# 10_-_CPU_-_JTAG_CONTROL.net
KiCad netlist of a schematic drawn in Altium Designer
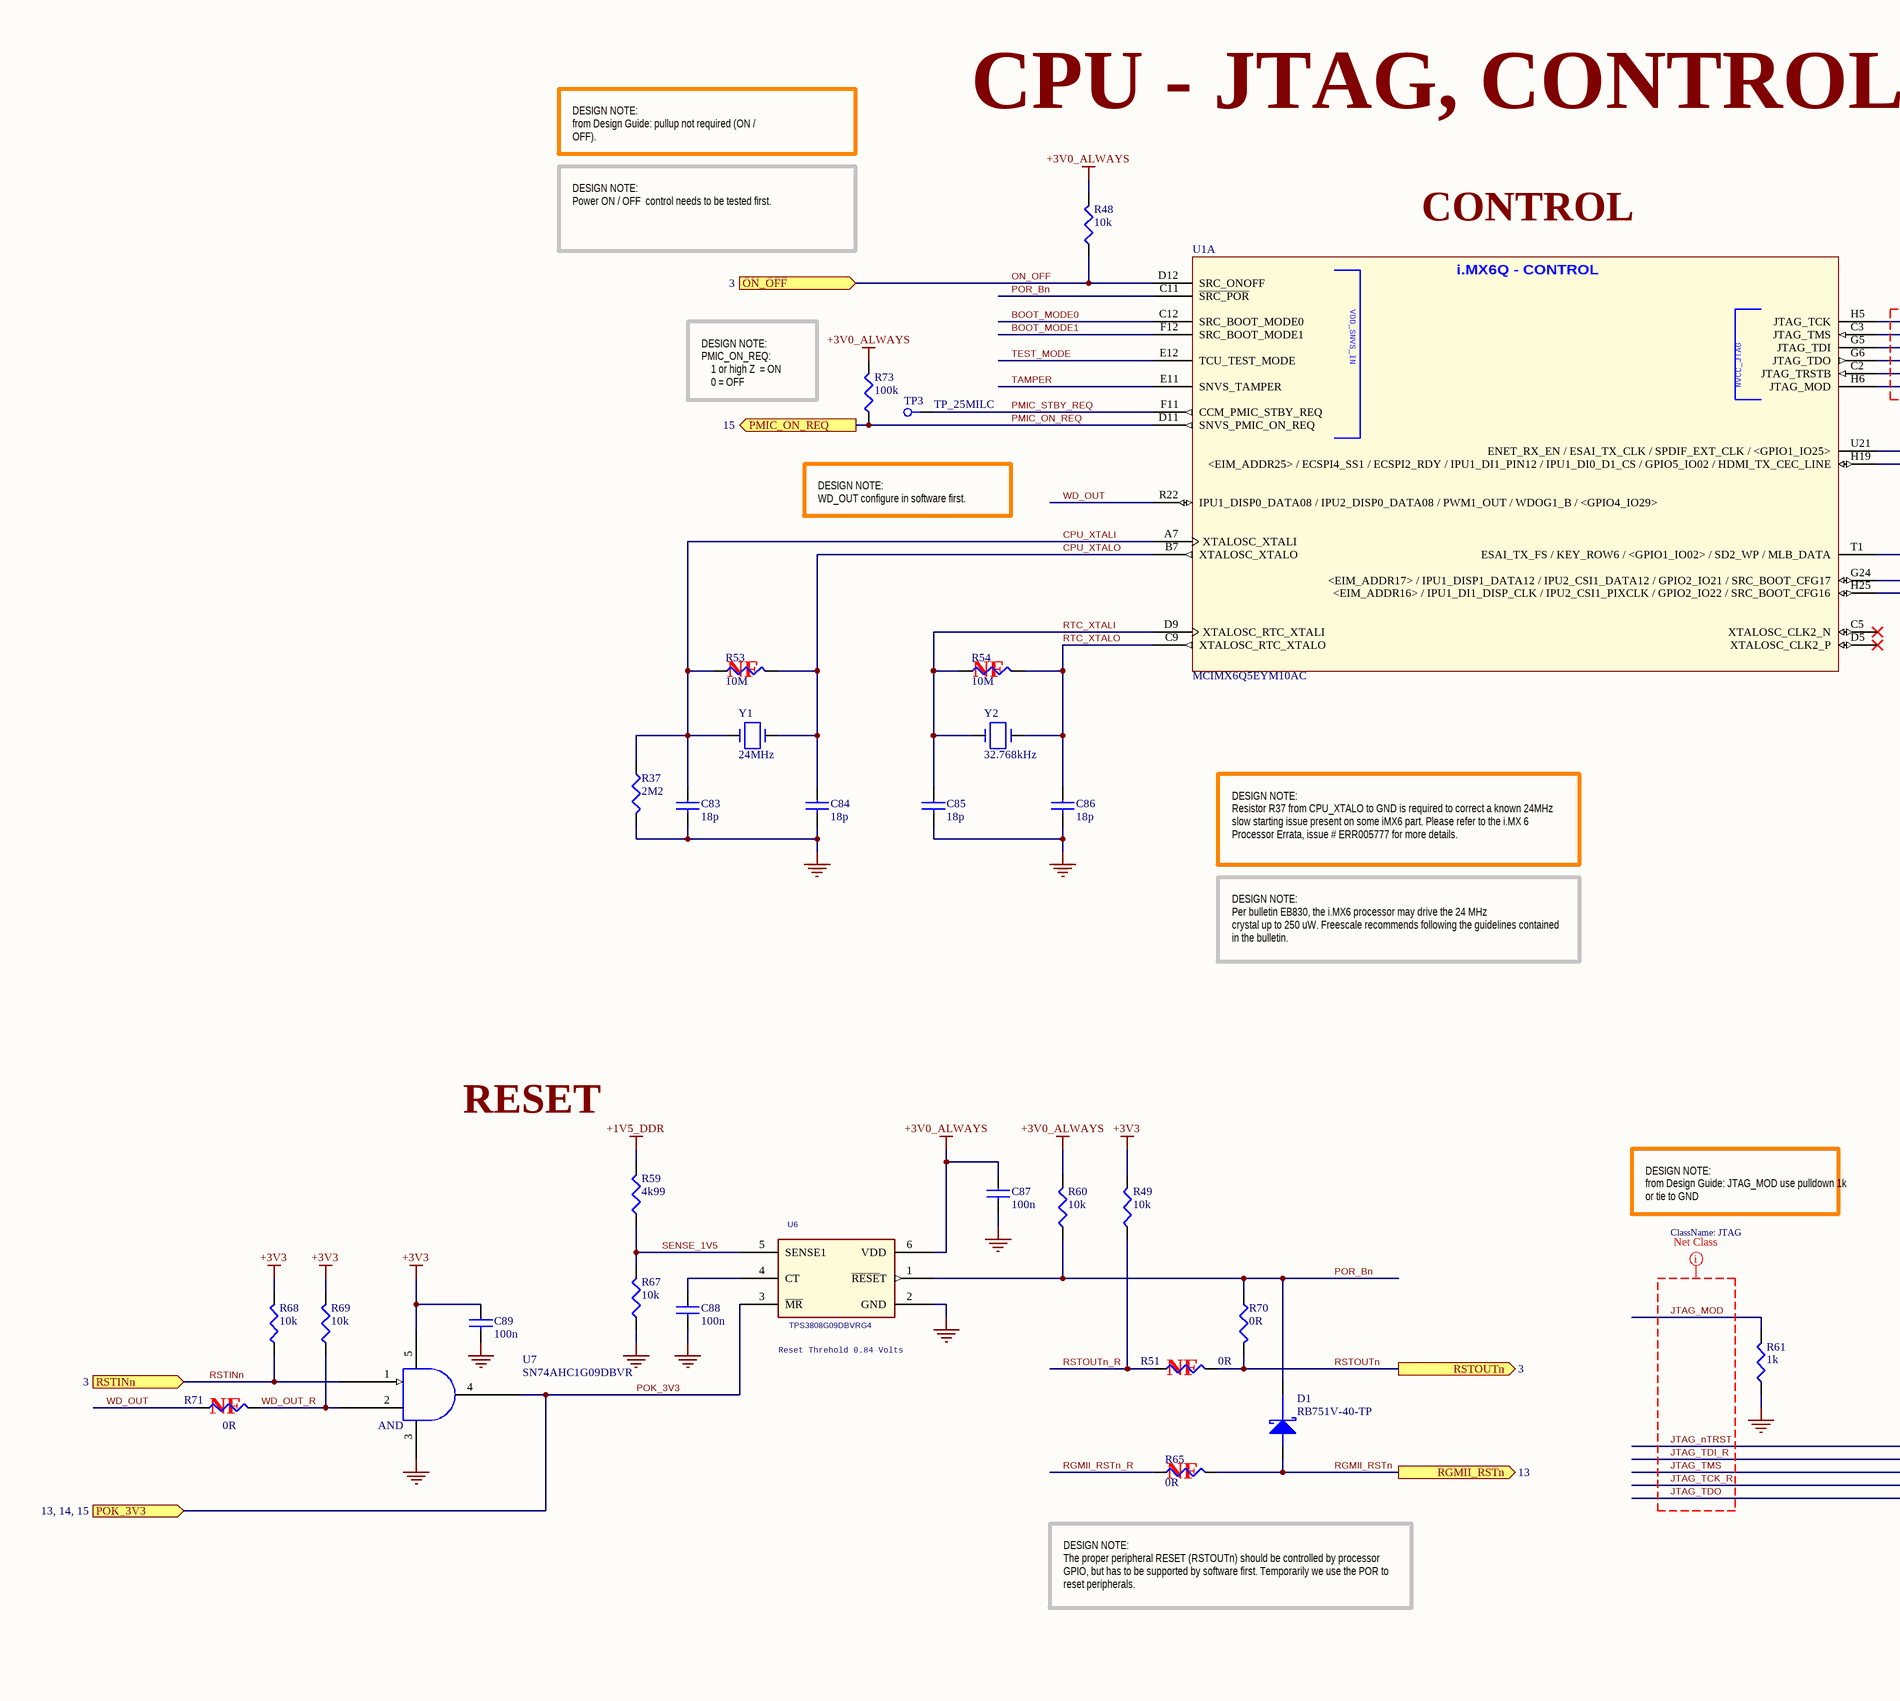
[diagram p0: [10] - CPU - JTAG, CONTROL.SchDoc, left]
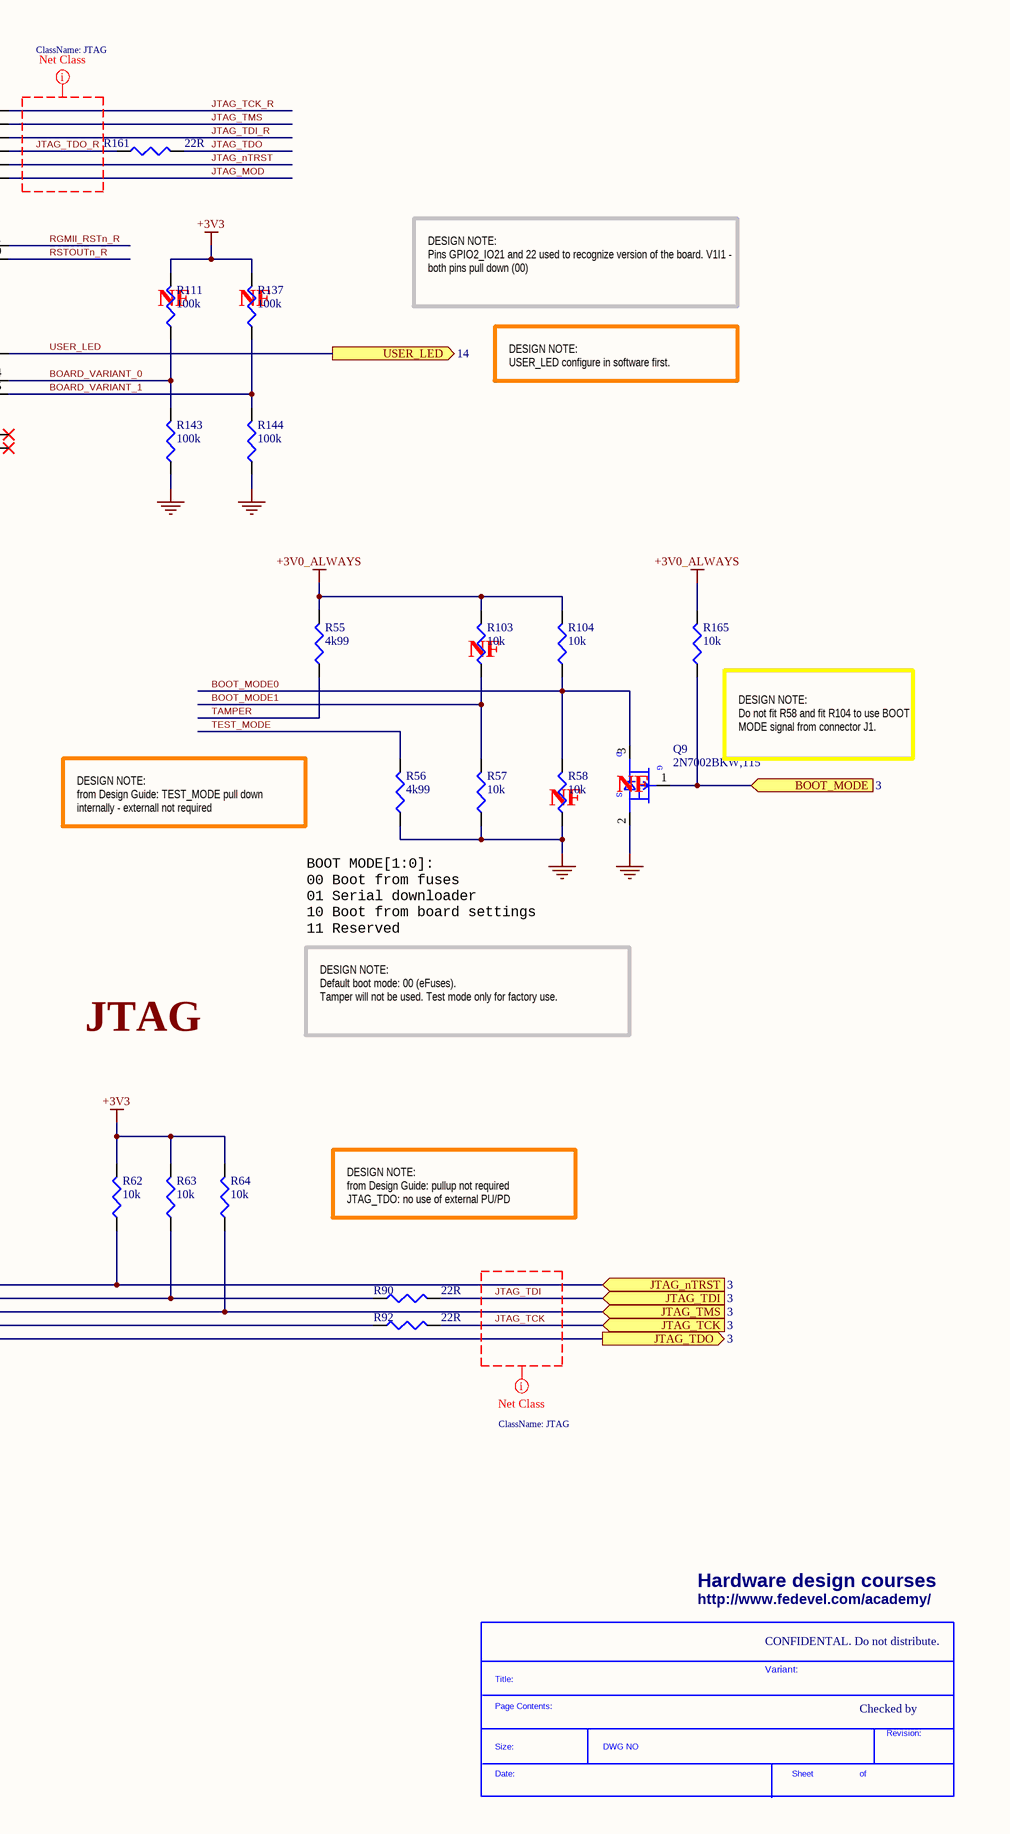
[diagram p1: [10] - CPU - JTAG, CONTROL.SchDoc, right]

(export (version "E")
  (design (tool "Eeschema 10.0.6"))
  (components
    (comp (ref "C83")
      (value "18p")
      (footprint "C0402")
      (description "CAP CER 18PF 50V C0G 5% 0402")
      (fields
        (field (name "MANUFACTURER") "TDK Corporation")
        (field (name "MANUFACTURER PART NUMBER") "C1005C0G1H180J")
      )
      (libsource (lib "iMX6 Rex_V1I1") (part "C1005C0G1H180J"))
    )
    (comp (ref "C84")
      (value "18p")
      (footprint "C0402")
      (description "CAP CER 18PF 50V C0G 5% 0402")
      (fields
        (field (name "MANUFACTURER") "TDK Corporation")
        (field (name "MANUFACTURER PART NUMBER") "C1005C0G1H180J")
      )
      (libsource (lib "iMX6 Rex_V1I1") (part "C1005C0G1H180J"))
    )
    (comp (ref "C85")
      (value "18p")
      (footprint "C0402")
      (description "CAP CER 18PF 50V C0G 5% 0402")
      (fields
        (field (name "MANUFACTURER") "TDK Corporation")
        (field (name "MANUFACTURER PART NUMBER") "C1005C0G1H180J")
      )
      (libsource (lib "iMX6 Rex_V1I1") (part "C1005C0G1H180J"))
    )
    (comp (ref "C86")
      (value "18p")
      (footprint "C0402")
      (description "CAP CER 18PF 50V C0G 5% 0402")
      (fields
        (field (name "MANUFACTURER") "TDK Corporation")
        (field (name "MANUFACTURER PART NUMBER") "C1005C0G1H180J")
      )
      (libsource (lib "iMX6 Rex_V1I1") (part "C1005C0G1H180J"))
    )
    (comp (ref "C87")
      (value "100n")
      (footprint "C0402")
      (description "CAP CER .10UF 50V X5R 10% 0402")
      (fields
        (field (name "MANUFACTURER") "TDK Corporation")
        (field (name "MANUFACTURER PART NUMBER") "C1005X5R1H104K")
      )
      (libsource (lib "iMX6 Rex_V1I1") (part "C1005X5R1H104K"))
    )
    (comp (ref "C88")
      (value "100n")
      (footprint "C0402")
      (description "CAP CER .10UF 50V X5R 10% 0402")
      (fields
        (field (name "MANUFACTURER") "TDK Corporation")
        (field (name "MANUFACTURER PART NUMBER") "C1005X5R1H104K")
      )
      (libsource (lib "iMX6 Rex_V1I1") (part "C1005X5R1H104K"))
    )
    (comp (ref "C89")
      (value "100n")
      (footprint "C0402")
      (description "CAP CER .10UF 50V X5R 10% 0402")
      (fields
        (field (name "MANUFACTURER") "TDK Corporation")
        (field (name "MANUFACTURER PART NUMBER") "C1005X5R1H104K")
      )
      (libsource (lib "iMX6 Rex_V1I1") (part "C1005X5R1H104K"))
    )
    (comp (ref "D1")
      (value "RB751V-40-TP")
      (footprint "SOD323")
      (description "DIODE SCHTKY 30MA 30V SOD-323")
      (fields
        (field (name "MANUFACTURER") "Micro Commercial Co")
        (field (name ".CHECKED PCB") "RF")
        (field (name ".CHECKED SCH") "RF")
      )
      (libsource (lib "iMX6 Rex_V1I1") (part "RB751V-40-TP"))
    )
    (comp (ref "Q9")
      (value "2N7002BKW,115")
      (footprint "SC70_SOT323")
      (description "MOSFET N-CH 60V 310MA SOT323")
      (fields
        (field (name "MANUFACTURER") "NXP Semiconductors")
        (field (name ".CHECKED PCB") "RF")
        (field (name ".CHECKED SCH") "RF")
      )
      (libsource (lib "iMX6 Rex_V1I1") (part "2N7002BKW,115"))
    )
    (comp (ref "R37")
      (value "2M2")
      (footprint "R0402")
      (description "RES 2.20M OHM 1/16W 1% 0402 SMD")
      (fields
        (field (name "MANUFACTURER") "Vishay Dale")
        (field (name "MANUFACTURER PART NUMBER") "CRCW04022M20FKED")
        (field (name ".CREATOR") "MM")
      )
      (libsource (lib "iMX6 Rex_V1I1") (part "CRCW04022M20FKED"))
    )
    (comp (ref "R48")
      (value "10k")
      (footprint "R0402")
      (description "RES 10.0K OHM 1/16W 1% 0402 SMD")
      (fields
        (field (name "MANUFACTURER") "Yageo")
        (field (name "MANUFACTURER PART NUMBER") "RC0402FR-0710KL")
      )
      (libsource (lib "iMX6 Rex_V1I1") (part "RC0402FR-0710KL"))
    )
    (comp (ref "R49")
      (value "10k")
      (footprint "R0402")
      (description "RES 10.0K OHM 1/16W 1% 0402 SMD")
      (fields
        (field (name "MANUFACTURER") "Yageo")
        (field (name "MANUFACTURER PART NUMBER") "RC0402FR-0710KL")
      )
      (libsource (lib "iMX6 Rex_V1I1") (part "RC0402FR-0710KL"))
    )
    (comp (ref "R51")
      (value "0R")
      (footprint "R0402")
      (description "RES 0.0 OHM 1/16W 0402 SMD")
      (fields
        (field (name "MANUFACTURER") "Yageo")
        (field (name "MANUFACTURER PART NUMBER") "RC0402JR-070RL")
      )
      (libsource (lib "iMX6 Rex_V1I1") (part "RC0402JR-070RL"))
    )
    (comp (ref "R53")
      (value "10M")
      (footprint "R0402")
      (description "RES 10.0M OHM 1/16W 1% 0402 SMD")
      (fields
        (field (name "MANUFACTURER") "Vishay Dale")
        (field (name "MANUFACTURER PART NUMBER") "CRCW040210M0FKED")
        (field (name ".CHECKED PCB") "RF")
        (field (name ".CHECKED SCH") "RF")
      )
      (libsource (lib "iMX6 Rex_V1I1") (part "CRCW040210M0FKED"))
    )
    (comp (ref "R54")
      (value "10M")
      (footprint "R0402")
      (description "RES 10.0M OHM 1/16W 1% 0402 SMD")
      (fields
        (field (name "MANUFACTURER") "Vishay Dale")
        (field (name "MANUFACTURER PART NUMBER") "CRCW040210M0FKED")
        (field (name ".CHECKED PCB") "RF")
        (field (name ".CHECKED SCH") "RF")
      )
      (libsource (lib "iMX6 Rex_V1I1") (part "CRCW040210M0FKED"))
    )
    (comp (ref "R55")
      (value "4k99")
      (footprint "R0402")
      (description "RES TF 4.99K OHM 1% 1/16W 0402")
      (fields
        (field (name "MANUFACTURER") "Stackpole Electronics Inc")
        (field (name "MANUFACTURER PART NUMBER") "RMCF0402FT4K99")
      )
      (libsource (lib "iMX6 Rex_V1I1") (part "RMCF0402FT4K99"))
    )
    (comp (ref "R56")
      (value "4k99")
      (footprint "R0402")
      (description "RES TF 4.99K OHM 1% 1/16W 0402")
      (fields
        (field (name "MANUFACTURER") "Stackpole Electronics Inc")
        (field (name "MANUFACTURER PART NUMBER") "RMCF0402FT4K99")
      )
      (libsource (lib "iMX6 Rex_V1I1") (part "RMCF0402FT4K99"))
    )
    (comp (ref "R57")
      (value "10k")
      (footprint "R0402")
      (description "RES 10.0K OHM 1/16W 1% 0402 SMD")
      (fields
        (field (name "MANUFACTURER") "Yageo")
        (field (name "MANUFACTURER PART NUMBER") "RC0402FR-0710KL")
      )
      (libsource (lib "iMX6 Rex_V1I1") (part "RC0402FR-0710KL"))
    )
    (comp (ref "R58")
      (value "10k")
      (footprint "R0402")
      (description "RES 10.0K OHM 1/16W 1% 0402 SMD")
      (fields
        (field (name "MANUFACTURER") "Yageo")
        (field (name "MANUFACTURER PART NUMBER") "RC0402FR-0710KL")
      )
      (libsource (lib "iMX6 Rex_V1I1") (part "RC0402FR-0710KL"))
    )
    (comp (ref "R59")
      (value "4k99")
      (footprint "R0402")
      (description "RES TF 4.99K OHM 1% 1/16W 0402")
      (fields
        (field (name "MANUFACTURER") "Stackpole Electronics Inc")
        (field (name "MANUFACTURER PART NUMBER") "RMCF0402FT4K99")
      )
      (libsource (lib "iMX6 Rex_V1I1") (part "RMCF0402FT4K99"))
    )
    (comp (ref "R60")
      (value "10k")
      (footprint "R0402")
      (description "RES 10.0K OHM 1/16W 1% 0402 SMD")
      (fields
        (field (name "MANUFACTURER") "Yageo")
        (field (name "MANUFACTURER PART NUMBER") "RC0402FR-0710KL")
      )
      (libsource (lib "iMX6 Rex_V1I1") (part "RC0402FR-0710KL"))
    )
    (comp (ref "R61")
      (value "1k")
      (footprint "R0402")
      (description "RES 1.00K OHM 1/16W 1% 0402 SMD")
      (fields
        (field (name "MANUFACTURER") "Yageo")
        (field (name "MANUFACTURER PART NUMBER") "RC0402FR-071KL")
      )
      (libsource (lib "iMX6 Rex_V1I1") (part "RC0402FR-071KL"))
    )
    (comp (ref "R62")
      (value "10k")
      (footprint "R0402")
      (description "RES 10.0K OHM 1/16W 1% 0402 SMD")
      (fields
        (field (name "MANUFACTURER") "Yageo")
        (field (name "MANUFACTURER PART NUMBER") "RC0402FR-0710KL")
      )
      (libsource (lib "iMX6 Rex_V1I1") (part "RC0402FR-0710KL"))
    )
    (comp (ref "R63")
      (value "10k")
      (footprint "R0402")
      (description "RES 10.0K OHM 1/16W 1% 0402 SMD")
      (fields
        (field (name "MANUFACTURER") "Yageo")
        (field (name "MANUFACTURER PART NUMBER") "RC0402FR-0710KL")
      )
      (libsource (lib "iMX6 Rex_V1I1") (part "RC0402FR-0710KL"))
    )
    (comp (ref "R64")
      (value "10k")
      (footprint "R0402")
      (description "RES 10.0K OHM 1/16W 1% 0402 SMD")
      (fields
        (field (name "MANUFACTURER") "Yageo")
        (field (name "MANUFACTURER PART NUMBER") "RC0402FR-0710KL")
      )
      (libsource (lib "iMX6 Rex_V1I1") (part "RC0402FR-0710KL"))
    )
    (comp (ref "R65")
      (value "0R")
      (footprint "R0402")
      (description "RES 0.0 OHM 1/16W 0402 SMD")
      (fields
        (field (name "MANUFACTURER") "Yageo")
        (field (name "MANUFACTURER PART NUMBER") "RC0402JR-070RL")
      )
      (libsource (lib "iMX6 Rex_V1I1") (part "RC0402JR-070RL"))
    )
    (comp (ref "R67")
      (value "10k")
      (footprint "R0402")
      (description "RES 10.0K OHM 1/16W 1% 0402 SMD")
      (fields
        (field (name "MANUFACTURER") "Yageo")
        (field (name "MANUFACTURER PART NUMBER") "RC0402FR-0710KL")
      )
      (libsource (lib "iMX6 Rex_V1I1") (part "RC0402FR-0710KL"))
    )
    (comp (ref "R68")
      (value "10k")
      (footprint "R0402")
      (description "RES 10.0K OHM 1/16W 1% 0402 SMD")
      (fields
        (field (name "MANUFACTURER") "Yageo")
        (field (name "MANUFACTURER PART NUMBER") "RC0402FR-0710KL")
      )
      (libsource (lib "iMX6 Rex_V1I1") (part "RC0402FR-0710KL"))
    )
    (comp (ref "R69")
      (value "10k")
      (footprint "R0402")
      (description "RES 10.0K OHM 1/16W 1% 0402 SMD")
      (fields
        (field (name "MANUFACTURER") "Yageo")
        (field (name "MANUFACTURER PART NUMBER") "RC0402FR-0710KL")
      )
      (libsource (lib "iMX6 Rex_V1I1") (part "RC0402FR-0710KL"))
    )
    (comp (ref "R70")
      (value "0R")
      (footprint "R0402")
      (description "RES 0.0 OHM 1/16W 0402 SMD")
      (fields
        (field (name "MANUFACTURER") "Yageo")
        (field (name "MANUFACTURER PART NUMBER") "RC0402JR-070RL")
      )
      (libsource (lib "iMX6 Rex_V1I1") (part "RC0402JR-070RL"))
    )
    (comp (ref "R71")
      (value "0R")
      (footprint "R0402")
      (description "RES 0.0 OHM 1/16W 0402 SMD")
      (fields
        (field (name "MANUFACTURER") "Yageo")
        (field (name "MANUFACTURER PART NUMBER") "RC0402JR-070RL")
      )
      (libsource (lib "iMX6 Rex_V1I1") (part "RC0402JR-070RL"))
    )
    (comp (ref "R73")
      (value "100k")
      (footprint "R0402")
      (description "RES 100K OHM 1/16W 1% 0402 SMD")
      (fields
        (field (name "MANUFACTURER") "Stackpole Electronics Inc")
        (field (name "MANUFACTURER PART NUMBER") "RMCF0402FT100K")
      )
      (libsource (lib "iMX6 Rex_V1I1") (part "RMCF0402FT100K"))
    )
    (comp (ref "R90")
      (value "22R")
      (footprint "R0402")
      (description "RES 22.0 OHM 1/16W 1% 0402 SMD")
      (fields
        (field (name "MANUFACTURER") "Yageo")
        (field (name "MANUFACTURER PART NUMBER") "RC0402FR-0722RL")
      )
      (libsource (lib "iMX6 Rex_V1I1") (part "RC0402FR-0722RL"))
    )
    (comp (ref "R92")
      (value "22R")
      (footprint "R0402")
      (description "RES 22.0 OHM 1/16W 1% 0402 SMD")
      (fields
        (field (name "MANUFACTURER") "Yageo")
        (field (name "MANUFACTURER PART NUMBER") "RC0402FR-0722RL")
      )
      (libsource (lib "iMX6 Rex_V1I1") (part "RC0402FR-0722RL"))
    )
    (comp (ref "R103")
      (value "10k")
      (footprint "R0402")
      (description "RES 10.0K OHM 1/16W 1% 0402 SMD")
      (fields
        (field (name "MANUFACTURER") "Yageo")
        (field (name "MANUFACTURER PART NUMBER") "RC0402FR-0710KL")
      )
      (libsource (lib "iMX6 Rex_V1I1") (part "RC0402FR-0710KL"))
    )
    (comp (ref "R104")
      (value "10k")
      (footprint "R0402")
      (description "RES 10.0K OHM 1/16W 1% 0402 SMD")
      (fields
        (field (name "MANUFACTURER") "Yageo")
        (field (name "MANUFACTURER PART NUMBER") "RC0402FR-0710KL")
      )
      (libsource (lib "iMX6 Rex_V1I1") (part "RC0402FR-0710KL"))
    )
    (comp (ref "R111")
      (value "100k")
      (footprint "R0402")
      (description "RES 100K OHM 1/16W 1% 0402 SMD")
      (fields
        (field (name "MANUFACTURER") "Stackpole Electronics Inc")
        (field (name "MANUFACTURER PART NUMBER") "RMCF0402FT100K")
      )
      (libsource (lib "iMX6 Rex_V1I1") (part "RMCF0402FT100K"))
    )
    (comp (ref "R137")
      (value "100k")
      (footprint "R0402")
      (description "RES 100K OHM 1/16W 1% 0402 SMD")
      (fields
        (field (name "MANUFACTURER") "Stackpole Electronics Inc")
        (field (name "MANUFACTURER PART NUMBER") "RMCF0402FT100K")
      )
      (libsource (lib "iMX6 Rex_V1I1") (part "RMCF0402FT100K"))
    )
    (comp (ref "R143")
      (value "100k")
      (footprint "R0402")
      (description "RES 100K OHM 1/16W 1% 0402 SMD")
      (fields
        (field (name "MANUFACTURER") "Stackpole Electronics Inc")
        (field (name "MANUFACTURER PART NUMBER") "RMCF0402FT100K")
      )
      (libsource (lib "iMX6 Rex_V1I1") (part "RMCF0402FT100K"))
    )
    (comp (ref "R144")
      (value "100k")
      (footprint "R0402")
      (description "RES 100K OHM 1/16W 1% 0402 SMD")
      (fields
        (field (name "MANUFACTURER") "Stackpole Electronics Inc")
        (field (name "MANUFACTURER PART NUMBER") "RMCF0402FT100K")
      )
      (libsource (lib "iMX6 Rex_V1I1") (part "RMCF0402FT100K"))
    )
    (comp (ref "R161")
      (value "22R")
      (footprint "R0402")
      (description "RES 22.0 OHM 1/16W 1% 0402 SMD")
      (fields
        (field (name "MANUFACTURER") "Yageo")
        (field (name "MANUFACTURER PART NUMBER") "RC0402FR-0722RL")
      )
      (libsource (lib "iMX6 Rex_V1I1") (part "RC0402FR-0722RL"))
    )
    (comp (ref "R165")
      (value "10k")
      (footprint "R0402")
      (description "RES 10.0K OHM 1/16W 1% 0402 SMD")
      (fields
        (field (name "MANUFACTURER") "Yageo")
        (field (name "MANUFACTURER PART NUMBER") "RC0402FR-0710KL")
      )
      (libsource (lib "iMX6 Rex_V1I1") (part "RC0402FR-0710KL"))
    )
    (comp (ref "TP3")
      (value "TP_25MILC")
      (footprint "TP_25C")
      (description "Test Point 25mil")
      (libsource (lib "iMX6 Rex_V1I1") (part "TP_25MILC"))
    )
    (comp (ref "U1")
      (value "MCIMX6Q5EYM10AC")
      (footprint "PBGA624")
      (description "IC MCU 32BIT ARM QUAD 624FCBGA")
      (fields
        (field (name "MANUFACTURER") "Freescale Semiconductor")
        (field (name ".CREATOR") "MM")
        (field (name ".CHECKED PCB") "MM, checked by RF")
        (field (name ".CHECKED SCH") "MM")
      )
      (libsource (lib "iMX6 Rex_V1I1") (part "MCIMX6Q5EYM10AC"))
    )
    (comp (ref "U6")
      (value "TPS3808G09DBVRG4")
      (footprint "DBV_SOT_23_6")
      (description "IC VOLT SUPERVISOR 0.9V SOT23-6")
      (fields (field (name "PART #") "102020-0009R") (field (name "MANUFACTURER") "Texas Instruments"))
      (libsource (lib "iMX6 Rex_V1I1") (part "TPS3808G09DBVR"))
    )
    (comp (ref "U7")
      (value "SN74AHC1G09DBVR")
      (footprint "DBV_SOT_23_5")
      (description "IC GATE AND SGL 2INP SOT23-5")
      (fields
        (field (name "MANUFACTURER") "Texas Instruments")
        (field (name ".CREATOR") "MM")
        (field (name ".CHECKED PCB") "RF, used by MM")
        (field (name ".CHECKED SCH") "MM, checked by RF")
      )
      (libsource (lib "iMX6 Rex_V1I1") (part "SN74AHC1G09DBVR"))
    )
    (comp (ref "Y1")
      (value "24MHz")
      (footprint "ABM7_v1_1")
      (description "CRYSTAL 24.0000MHZ 18PF SMD")
      (fields
        (field (name "MANUFACTURER") "Abracon Corporation")
        (field (name "MANUFACTURER PART NUMBER") "ABM7-24.000MHZ-D-2-Y-T")
        (field (name ".CREATOR") "MM")
        (field (name ".CHECKED PCB") "RF, used by MM")
        (field (name ".CHECKED SCH") "MM, checked by RF")
      )
      (libsource (lib "iMX6 Rex_V1I1") (part "ABM7-24.000MHZ-D-2-Y-T"))
    )
    (comp (ref "Y2")
      (value "32.768kHz")
      (footprint "ABS06")
      (description "CRYSTAL 32.768 KHZ 9.0 PF SMD")
      (fields
        (field (name "MANUFACTURER") "Abracon Corporation")
        (field (name "MANUFACTURER PART NUMBER") "ABS06-32.768KHZ-9-1-T")
      )
      (libsource (lib "iMX6 Rex_V1I1") (part "ABS06-32.768KHZ-9-1-T"))
    )
  )
  (nets
    (net (code "1") (name "+1V5_DDR") (class "Default")
      (node (ref "R59") (pin "2") (pinfunction "2_2") (pintype "passive"))
    )
    (net (code "2") (name "+3V0_ALWAYS") (class "Default")
      (node (ref "C87") (pin "1") (pinfunction "1_1") (pintype "passive"))
      (node (ref "R103") (pin "2") (pinfunction "2_2") (pintype "passive"))
      (node (ref "R104") (pin "2") (pinfunction "2_2") (pintype "passive"))
      (node (ref "R165") (pin "2") (pinfunction "2_2") (pintype "passive"))
      (node (ref "R48") (pin "2") (pinfunction "2_2") (pintype "passive"))
      (node (ref "R55") (pin "2") (pinfunction "2_2") (pintype "passive"))
      (node (ref "R60") (pin "2") (pinfunction "2_2") (pintype "passive"))
      (node (ref "R73") (pin "2") (pinfunction "2_2") (pintype "passive"))
      (node (ref "U6") (pin "6") (pinfunction "VDD_6") (pintype "passive"))
    )
    (net (code "3") (name "+3V3") (class "Default")
      (node (ref "C89") (pin "1") (pinfunction "1_1") (pintype "passive"))
      (node (ref "R111") (pin "2") (pinfunction "2_2") (pintype "passive"))
      (node (ref "R137") (pin "2") (pinfunction "2_2") (pintype "passive"))
      (node (ref "R49") (pin "2") (pinfunction "2_2") (pintype "passive"))
      (node (ref "R62") (pin "2") (pinfunction "2_2") (pintype "passive"))
      (node (ref "R63") (pin "2") (pinfunction "2_2") (pintype "passive"))
      (node (ref "R64") (pin "2") (pinfunction "2_2") (pintype "passive"))
      (node (ref "R68") (pin "2") (pinfunction "2_2") (pintype "passive"))
      (node (ref "R69") (pin "2") (pinfunction "2_2") (pintype "passive"))
      (node (ref "U7") (pin "5") (pinfunction "VCC_5") (pintype "power_in"))
    )
    (net (code "4") (name "/BOARD_VARIANT_0") (class "Default")
      (node (ref "R111") (pin "1") (pinfunction "1_1") (pintype "passive"))
      (node (ref "R143") (pin "2") (pinfunction "2_2") (pintype "passive"))
      (node (ref "U1") (pin "G24") (pinfunction "<EIM_ADDR17>_/_IPU1_DISP1_DATA12_/_IPU2_CSI1_DATA12_/_GPIO2_IO21_/_SRC_BOOT_CFG17_G24") (pintype "bidirectional"))
    )
    (net (code "5") (name "/BOARD_VARIANT_1") (class "Default")
      (node (ref "R137") (pin "1") (pinfunction "1_1") (pintype "passive"))
      (node (ref "R144") (pin "2") (pinfunction "2_2") (pintype "passive"))
      (node (ref "U1") (pin "H25") (pinfunction "<EIM_ADDR16>_/_IPU1_DI1_DISP_CLK_/_IPU2_CSI1_PIXCLK_/_GPIO2_IO22_/_SRC_BOOT_CFG16_H25") (pintype "bidirectional"))
    )
    (net (code "6") (name "/BOOT_MODE") (class "Default")
      (node (ref "Q9") (pin "1") (pinfunction "GATE_1") (pintype "passive"))
      (node (ref "R165") (pin "1") (pinfunction "1_1") (pintype "passive"))
    )
    (net (code "7") (name "/BOOT_MODE0") (class "Default")
      (node (ref "Q9") (pin "3") (pinfunction "DRAIN_3") (pintype "passive"))
      (node (ref "R104") (pin "1") (pinfunction "1_1") (pintype "passive"))
      (node (ref "R58") (pin "2") (pinfunction "2_2") (pintype "passive"))
      (node (ref "U1") (pin "C12") (pinfunction "SRC_BOOT_MODE0_C12") (pintype "passive"))
    )
    (net (code "8") (name "/BOOT_MODE1") (class "Default")
      (node (ref "R103") (pin "1") (pinfunction "1_1") (pintype "passive"))
      (node (ref "R57") (pin "2") (pinfunction "2_2") (pintype "passive"))
      (node (ref "U1") (pin "F12") (pinfunction "SRC_BOOT_MODE1_F12") (pintype "passive"))
    )
    (net (code "9") (name "/CPU_XTALI") (class "Default")
      (node (ref "C83") (pin "1") (pinfunction "1_1") (pintype "passive"))
      (node (ref "R37") (pin "1") (pinfunction "1_1") (pintype "passive"))
      (node (ref "R53") (pin "1") (pinfunction "1_1") (pintype "passive"))
      (node (ref "U1") (pin "A7") (pinfunction "XTALOSC_XTALI_A7") (pintype "passive"))
      (node (ref "Y1") (pin "1") (pinfunction "1_1") (pintype "passive"))
    )
    (net (code "10") (name "/CPU_XTALO") (class "Default")
      (node (ref "C84") (pin "1") (pinfunction "1_1") (pintype "passive"))
      (node (ref "R53") (pin "2") (pinfunction "2_2") (pintype "passive"))
      (node (ref "U1") (pin "B7") (pinfunction "XTALOSC_XTALO_B7") (pintype "output"))
      (node (ref "Y1") (pin "2") (pinfunction "2_2") (pintype "passive"))
    )
    (net (code "11") (name "/JTAG_MOD") (class "Default")
      (node (ref "R61") (pin "2") (pinfunction "2_2") (pintype "passive"))
      (node (ref "U1") (pin "H6") (pinfunction "JTAG_MOD_H6") (pintype "passive"))
    )
    (net (code "12") (name "/JTAG_TCK") (class "Default")
      (node (ref "R92") (pin "2") (pinfunction "2_2") (pintype "passive"))
    )
    (net (code "13") (name "/JTAG_TCK_R") (class "Default")
      (node (ref "R92") (pin "1") (pinfunction "1_1") (pintype "passive"))
      (node (ref "U1") (pin "H5") (pinfunction "JTAG_TCK_H5") (pintype "passive"))
    )
    (net (code "14") (name "/JTAG_TDI") (class "Default")
      (node (ref "R90") (pin "2") (pinfunction "2_2") (pintype "passive"))
    )
    (net (code "15") (name "/JTAG_TDI_R") (class "Default")
      (node (ref "R63") (pin "1") (pinfunction "1_1") (pintype "passive"))
      (node (ref "R90") (pin "1") (pinfunction "1_1") (pintype "passive"))
      (node (ref "U1") (pin "G5") (pinfunction "JTAG_TDI_G5") (pintype "passive"))
    )
    (net (code "16") (name "/JTAG_TDO") (class "Default")
      (node (ref "R161") (pin "2") (pinfunction "2_2") (pintype "passive"))
    )
    (net (code "17") (name "/JTAG_TDO_R") (class "Default")
      (node (ref "R161") (pin "1") (pinfunction "1_1") (pintype "passive"))
      (node (ref "U1") (pin "G6") (pinfunction "JTAG_TDO_G6") (pintype "output"))
    )
    (net (code "18") (name "/JTAG_TMS") (class "Default")
      (node (ref "R64") (pin "1") (pinfunction "1_1") (pintype "passive"))
      (node (ref "U1") (pin "C3") (pinfunction "JTAG_TMS_C3") (pintype "input"))
    )
    (net (code "19") (name "/JTAG_nTRST") (class "Default")
      (node (ref "R62") (pin "1") (pinfunction "1_1") (pintype "passive"))
      (node (ref "U1") (pin "C2") (pinfunction "JTAG_TRSTB_C2") (pintype "input"))
    )
    (net (code "20") (name "/ON_OFF") (class "Default")
      (node (ref "R48") (pin "1") (pinfunction "1_1") (pintype "passive"))
      (node (ref "U1") (pin "D12") (pinfunction "SRC_ONOFF_D12") (pintype "passive"))
    )
    (net (code "21") (name "/PMIC_ON_REQ") (class "Default")
      (node (ref "R73") (pin "1") (pinfunction "1_1") (pintype "passive"))
      (node (ref "U1") (pin "D11") (pinfunction "SNVS_PMIC_ON_REQ_D11") (pintype "output"))
    )
    (net (code "22") (name "/PMIC_STBY_REQ") (class "Default")
      (node (ref "TP3") (pin "1") (pinfunction "1_1") (pintype "passive"))
      (node (ref "U1") (pin "F11") (pinfunction "CCM_PMIC_STBY_REQ_F11") (pintype "output"))
    )
    (net (code "23") (name "/POK_3V3") (class "Default")
      (node (ref "U6") (pin "3") (pinfunction "~{MR}_3") (pintype "passive"))
      (node (ref "U7") (pin "4") (pinfunction "Y_4") (pintype "passive"))
    )
    (net (code "24") (name "/POR_Bn") (class "Default")
      (node (ref "D1") (pin "1") (pinfunction "cathode_1") (pintype "passive"))
      (node (ref "R60") (pin "1") (pinfunction "1_1") (pintype "passive"))
      (node (ref "R70") (pin "1") (pinfunction "1_1") (pintype "passive"))
      (node (ref "U1") (pin "C11") (pinfunction "~{SRC_POR}_C11") (pintype "passive"))
      (node (ref "U6") (pin "1") (pinfunction "~{RESE}T_1") (pintype "output"))
    )
    (net (code "25") (name "/RGMII_RSTn") (class "Default")
      (node (ref "D1") (pin "2") (pinfunction "ANODE_2") (pintype "passive"))
      (node (ref "R65") (pin "2") (pinfunction "2_2") (pintype "passive"))
    )
    (net (code "26") (name "/RGMII_RSTn_R") (class "Default")
      (node (ref "R65") (pin "1") (pinfunction "1_1") (pintype "passive"))
      (node (ref "U1") (pin "U21") (pinfunction "ENET_RX_EN_/_ESAI_TX_CLK_/_SPDIF_EXT_CLK_/_<GPIO1_IO25>_U21") (pintype "passive"))
    )
    (net (code "27") (name "/RSTINn") (class "Default")
      (node (ref "R68") (pin "1") (pinfunction "1_1") (pintype "passive"))
      (node (ref "U7") (pin "1") (pinfunction "A_1") (pintype "input"))
    )
    (net (code "28") (name "/RSTOUTn") (class "Default")
      (node (ref "R51") (pin "2") (pinfunction "2_2") (pintype "passive"))
      (node (ref "R70") (pin "2") (pinfunction "2_2") (pintype "passive"))
    )
    (net (code "29") (name "/RSTOUTn_R") (class "Default")
      (node (ref "R49") (pin "1") (pinfunction "1_1") (pintype "passive"))
      (node (ref "R51") (pin "1") (pinfunction "1_1") (pintype "passive"))
      (node (ref "U1") (pin "H19") (pinfunction "<EIM_ADDR25>_/_ECSPI4_SS1_/_ECSPI2_RDY_/_IPU1_DI1_PIN12_/_IPU1_DI0_D1_CS_/_GPIO5_IO02_/_HDMI_TX_CEC_LINE_H19") (pintype "bidirectional"))
    )
    (net (code "30") (name "/RTC_XTALI") (class "Default")
      (node (ref "C85") (pin "1") (pinfunction "1_1") (pintype "passive"))
      (node (ref "R54") (pin "1") (pinfunction "1_1") (pintype "passive"))
      (node (ref "U1") (pin "D9") (pinfunction "XTALOSC_RTC_XTALI_D9") (pintype "passive"))
      (node (ref "Y2") (pin "1") (pinfunction "1_1") (pintype "passive"))
    )
    (net (code "31") (name "/RTC_XTALO") (class "Default")
      (node (ref "C86") (pin "1") (pinfunction "1_1") (pintype "passive"))
      (node (ref "R54") (pin "2") (pinfunction "2_2") (pintype "passive"))
      (node (ref "U1") (pin "C9") (pinfunction "XTALOSC_RTC_XTALO_C9") (pintype "output"))
      (node (ref "Y2") (pin "2") (pinfunction "2_2") (pintype "passive"))
    )
    (net (code "32") (name "/SENSE_1V5") (class "Default")
      (node (ref "R59") (pin "1") (pinfunction "1_1") (pintype "passive"))
      (node (ref "R67") (pin "2") (pinfunction "2_2") (pintype "passive"))
      (node (ref "U6") (pin "5") (pinfunction "SENSE1_5") (pintype "passive"))
    )
    (net (code "33") (name "/TAMPER") (class "Default")
      (node (ref "R55") (pin "1") (pinfunction "1_1") (pintype "passive"))
      (node (ref "U1") (pin "E11") (pinfunction "SNVS_TAMPER_E11") (pintype "passive"))
    )
    (net (code "34") (name "/TEST_MODE") (class "Default")
      (node (ref "R56") (pin "2") (pinfunction "2_2") (pintype "passive"))
      (node (ref "U1") (pin "E12") (pinfunction "TCU_TEST_MODE_E12") (pintype "passive"))
    )
    (net (code "35") (name "/USER_LED") (class "Default")
      (node (ref "U1") (pin "T1") (pinfunction "ESAI_TX_FS_/_KEY_ROW6_/_<GPIO1_IO02>_/_SD2_WP_/_MLB_DATA_T1") (pintype "passive"))
    )
    (net (code "36") (name "/WD_OUT") (class "Default")
      (node (ref "R71") (pin "1") (pinfunction "1_1") (pintype "passive"))
      (node (ref "U1") (pin "R22") (pinfunction "IPU1_DISP0_DATA08_/_IPU2_DISP0_DATA08_/_PWM1_OUT_/_WDOG1_B_/_<GPIO4_IO29>_R22") (pintype "bidirectional"))
    )
    (net (code "37") (name "/WD_OUT_R") (class "Default")
      (node (ref "R69") (pin "1") (pinfunction "1_1") (pintype "passive"))
      (node (ref "R71") (pin "2") (pinfunction "2_2") (pintype "passive"))
      (node (ref "U7") (pin "2") (pinfunction "B_2") (pintype "passive"))
    )
    (net (code "38") (name "GND") (class "Default")
      (node (ref "C83") (pin "2") (pinfunction "2_2") (pintype "passive"))
      (node (ref "C84") (pin "2") (pinfunction "2_2") (pintype "passive"))
      (node (ref "C85") (pin "2") (pinfunction "2_2") (pintype "passive"))
      (node (ref "C86") (pin "2") (pinfunction "2_2") (pintype "passive"))
      (node (ref "C87") (pin "2") (pinfunction "2_2") (pintype "passive"))
      (node (ref "C88") (pin "2") (pinfunction "2_2") (pintype "passive"))
      (node (ref "C89") (pin "2") (pinfunction "2_2") (pintype "passive"))
      (node (ref "Q9") (pin "2") (pinfunction "SOURCE_2") (pintype "passive"))
      (node (ref "R143") (pin "1") (pinfunction "1_1") (pintype "passive"))
      (node (ref "R144") (pin "1") (pinfunction "1_1") (pintype "passive"))
      (node (ref "R37") (pin "2") (pinfunction "2_2") (pintype "passive"))
      (node (ref "R56") (pin "1") (pinfunction "1_1") (pintype "passive"))
      (node (ref "R57") (pin "1") (pinfunction "1_1") (pintype "passive"))
      (node (ref "R58") (pin "1") (pinfunction "1_1") (pintype "passive"))
      (node (ref "R61") (pin "1") (pinfunction "1_1") (pintype "passive"))
      (node (ref "R67") (pin "1") (pinfunction "1_1") (pintype "passive"))
      (node (ref "U6") (pin "2") (pinfunction "GND_2") (pintype "passive"))
      (node (ref "U7") (pin "3") (pinfunction "GND_3") (pintype "power_in"))
    )
    (net (code "39") (name "Net-(U6-CT)") (class "Default")
      (node (ref "C88") (pin "1") (pinfunction "1_1") (pintype "passive"))
      (node (ref "U6") (pin "4") (pinfunction "CT_4") (pintype "passive"))
    )
    (net (code "40") (name "unconnected-(U1A-XTALOSC_CLK2_N-PadC5)") (class "Default")
      (node (ref "U1") (pin "C5") (pinfunction "XTALOSC_CLK2_N_C5") (pintype "bidirectional+no_connect"))
    )
    (net (code "41") (name "unconnected-(U1A-XTALOSC_CLK2_P-PadD5)") (class "Default")
      (node (ref "U1") (pin "D5") (pinfunction "XTALOSC_CLK2_P_D5") (pintype "bidirectional+no_connect"))
    )
  )
)
